# MMI.net
KiCad netlist of a schematic drawn in Altium Designer
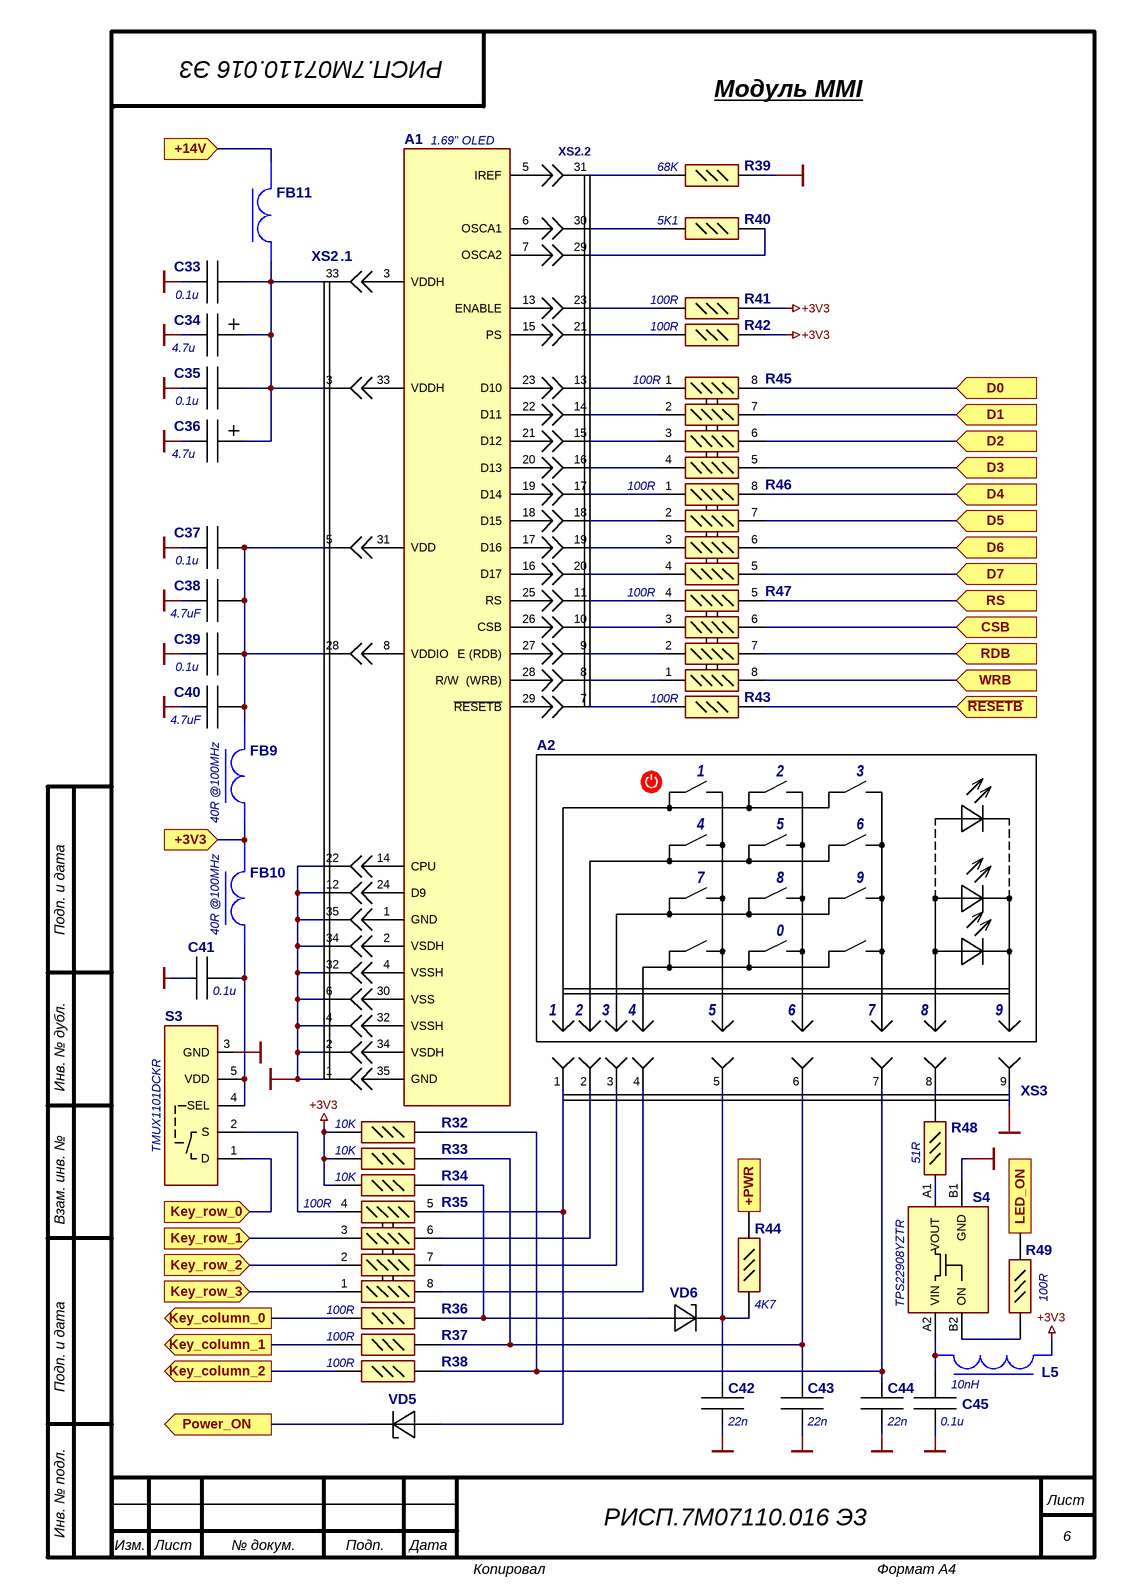
[diagram p0: Модуль MMI.SchDoc]

(export (version "E")
  (design (tool "Eeschema 10.0.6"))
  (components
    (comp (ref "A1")
      (value "1.69\" OLED")
      (fields (field (name "MANUFACTURER_PART_NUMBER") "NHD-1.69-160128G"))
      (libsource (lib "Other") (part "NHD-1.69-160128G"))
    )
    (comp (ref "A2")
      (value "~")
      (fields (field (name "MANUFACTURER_PART_NUMBER") "Клавиатура 5042 ТЕИЯ.464511.002 ТЗ"))
      (libsource (lib "Other") (part "Клавиатура 3x4 (Заказ №...)"))
    )
    (comp (ref "C33")
      (value "0.1u")
      (footprint ":CAP0402 100x50x50")
      (description "±10% 25V Ceramic Capacitor X7R 0402 (1005 Metric)")
      (fields
        (field (name "MANUFACTURER_PART_NUMBER") "GRM155R71E104KE14J")
        (field (name "MOUSER PART NUMBER") "81-GRM155R71E104KE4J")
      )
      (libsource (lib "Capacitors 0402") (part "GRM155R71E104KE14J"))
    )
    (comp (ref "C34")
      (value "4.7u")
      (footprint ":CAP1206 C3216-18")
      (description "4.7µF Molded Tantalum Capacitors 25V 1206 (3216 Metric) 50mOhm")
      (fields (field (name "MANUFACTURER_PART_NUMBER") "T491A475K025AT"))
      (libsource (lib "Capacitors 1206") (part "T491A475K025AT"))
    )
    (comp (ref "C35")
      (value "0.1u")
      (footprint ":CAP0402 100x50x50")
      (description "±10% 25V Ceramic Capacitor X7R 0402 (1005 Metric)")
      (fields
        (field (name "MANUFACTURER_PART_NUMBER") "GRM155R71E104KE14J")
        (field (name "MOUSER PART NUMBER") "81-GRM155R71E104KE4J")
      )
      (libsource (lib "Capacitors 0402") (part "GRM155R71E104KE14J"))
    )
    (comp (ref "C36")
      (value "4.7u")
      (footprint ":CAP1206 C3216-18")
      (description "4.7µF Molded Tantalum Capacitors 25V 1206 (3216 Metric) 50mOhm")
      (fields (field (name "MANUFACTURER_PART_NUMBER") "T491A475K025AT"))
      (libsource (lib "Capacitors 1206") (part "T491A475K025AT"))
    )
    (comp (ref "C37")
      (value "0.1u")
      (footprint ":CAP0402 100x50x50")
      (description "±10% 25V Ceramic Capacitor X7R 0402 (1005 Metric)")
      (fields
        (field (name "MANUFACTURER_PART_NUMBER") "GRM155R71E104KE14J")
        (field (name "MOUSER PART NUMBER") "81-GRM155R71E104KE4J")
      )
      (libsource (lib "Capacitors 0402") (part "GRM155R71E104KE14J"))
    )
    (comp (ref "C38")
      (value "4.7uF")
      (footprint ":CAP0805 C2012X125")
      (description "CAP CER 4.7uF 25V X7R 0805")
      (fields (field (name "MANUFACTURER_PART_NUMBER") "GRM21BZ71E475KE15L"))
      (libsource (lib "Capacitors 0805") (part "GRM21BZ71E475KE15L"))
    )
    (comp (ref "C39")
      (value "0.1u")
      (footprint ":CAP0402 100x50x50")
      (description "±10% 25V Ceramic Capacitor X7R 0402 (1005 Metric)")
      (fields
        (field (name "MANUFACTURER_PART_NUMBER") "GRM155R71E104KE14J")
        (field (name "MOUSER PART NUMBER") "81-GRM155R71E104KE4J")
      )
      (libsource (lib "Capacitors 0402") (part "GRM155R71E104KE14J"))
    )
    (comp (ref "C40")
      (value "4.7uF")
      (footprint ":CAP0805 C2012X125")
      (description "CAP CER 4.7uF 25V X7R 0805")
      (fields (field (name "MANUFACTURER_PART_NUMBER") "GRM21BZ71E475KE15L"))
      (libsource (lib "Capacitors 0805") (part "GRM21BZ71E475KE15L"))
    )
    (comp (ref "C41")
      (value "0.1u")
      (footprint ":CAP0402 100x50x50")
      (description "±10% 25V Ceramic Capacitor X7R 0402 (1005 Metric)")
      (fields
        (field (name "MANUFACTURER_PART_NUMBER") "GRM155R71E104KE14J")
        (field (name "MOUSER PART NUMBER") "81-GRM155R71E104KE4J")
      )
      (libsource (lib "Capacitors 0402") (part "GRM155R71E104KE14J"))
    )
    (comp (ref "C42")
      (value "22n")
      (footprint ":CAP0402 100x50x50")
      (description "CAP CER  25V X7R 0402")
      (fields (field (name "MANUFACTURER_PART_NUMBER") "GCM155R71E223KA55D"))
      (libsource (lib "Capacitors 0402") (part "GCM155R71E223KA55D"))
    )
    (comp (ref "C43")
      (value "22n")
      (footprint ":CAP0402 100x50x50")
      (description "CAP CER  25V X7R 0402")
      (fields (field (name "MANUFACTURER_PART_NUMBER") "GCM155R71E223KA55D"))
      (libsource (lib "Capacitors 0402") (part "GCM155R71E223KA55D"))
    )
    (comp (ref "C44")
      (value "22n")
      (footprint ":CAP0402 100x50x50")
      (description "CAP CER  25V X7R 0402")
      (fields (field (name "MANUFACTURER_PART_NUMBER") "GCM155R71E223KA55D"))
      (libsource (lib "Capacitors 0402") (part "GCM155R71E223KA55D"))
    )
    (comp (ref "C45")
      (value "0.1u")
      (footprint ":CAP0402 100x50x50")
      (description "±10% 25V Ceramic Capacitor X7R 0402 (1005 Metric)")
      (fields
        (field (name "MANUFACTURER_PART_NUMBER") "GRM155R71E104KE14J")
        (field (name "MOUSER PART NUMBER") "81-GRM155R71E104KE4J")
      )
      (libsource (lib "Capacitors 0402") (part "GRM155R71E104KE14J"))
    )
    (comp (ref "FB9")
      (value "40R @100MHz")
      (footprint ":FER MMZ1005Y400CTD25")
      (description "40 Ohms @ 100MHz 1 Signal Line Ferrite Bead 0402 (1005 Metric) 550mA 100mOhm")
      (fields
        (field (name "MANUFACTURER_PART_NUMBER") "MMZ1005Y400CTD25")
        (field (name "MOUSER PART NUMBER") "810-MMZ1005Y400CTD25")
      )
      (libsource (lib "Ferrite Bead") (part "MMZ1005Y400CTD25"))
    )
    (comp (ref "FB10")
      (value "40R @100MHz")
      (footprint ":FER MMZ1005Y400CTD25")
      (description "40 Ohms @ 100MHz 1 Signal Line Ferrite Bead 0402 (1005 Metric) 550mA 100mOhm")
      (fields
        (field (name "MANUFACTURER_PART_NUMBER") "MMZ1005Y400CTD25")
        (field (name "MOUSER PART NUMBER") "810-MMZ1005Y400CTD25")
      )
      (libsource (lib "Ferrite Bead") (part "MMZ1005Y400CTD25"))
    )
    (comp (ref "FB11")
      (value "40R @100MHz")
      (footprint ":FER MMZ1005Y400CTD25")
      (description "40 Ohms @ 100MHz 1 Signal Line Ferrite Bead 0402 (1005 Metric) 550mA 100mOhm")
      (fields
        (field (name "MANUFACTURER_PART_NUMBER") "MMZ1005Y400CTD25")
        (field (name "MOUSER PART NUMBER") "810-MMZ1005Y400CTD25")
      )
      (libsource (lib "Ferrite Bead") (part "MMZ1005Y400CTD25"))
    )
    (comp (ref "L5")
      (value "10nH")
      (footprint ":IND 0402")
      (description "Unshielded Multilayer Inductor 0402 5%")
      (fields (field (name "MANUFACTURER_PART_NUMBER") "LQG15HN10NJ02D"))
      (libsource (lib "Inductance 0402") (part "LQG15HN10NJ02D"))
    )
    (comp (ref "R32")
      (value "RC0402FR-07")
      (footprint ":RES0402")
      (fields (field (name "MANUFACTURER_PART_NUMBER (PART 2: VALUE)") "10K"))
      (libsource (lib "") (part "RC0402FR-07_1"))
    )
    (comp (ref "R33")
      (value "RC0402FR-07")
      (footprint ":RES0402")
      (fields (field (name "MANUFACTURER_PART_NUMBER (PART 2: VALUE)") "10K"))
      (libsource (lib "") (part "RC0402FR-07_1"))
    )
    (comp (ref "R34")
      (value "RC0402FR-07")
      (footprint ":RES0402")
      (fields (field (name "MANUFACTURER_PART_NUMBER (PART 2: VALUE)") "10K"))
      (libsource (lib "") (part "RC0402FR-07_1"))
    )
    (comp (ref "R35")
      (value "100R")
      (footprint ":RES0402x4")
      (fields
        (field (name "MANUFACTURER_PART_NUMBER") "EXB-N8V101JX")
        (field (name "MOUSER PART NUMBER") "667-EXB-N8V101JX")
      )
      (libsource (lib "Resistors Arrays") (part "EXB-N8V101JX"))
    )
    (comp (ref "R36")
      (value "RC0402FR-07")
      (footprint ":RES0402")
      (fields (field (name "MANUFACTURER_PART_NUMBER (PART 2: VALUE)") "100R"))
      (libsource (lib "") (part "RC0402FR-07_2"))
    )
    (comp (ref "R37")
      (value "RC0402FR-07")
      (footprint ":RES0402")
      (fields (field (name "MANUFACTURER_PART_NUMBER (PART 2: VALUE)") "100R"))
      (libsource (lib "") (part "RC0402FR-07_2"))
    )
    (comp (ref "R38")
      (value "RC0402FR-07")
      (footprint ":RES0402")
      (fields (field (name "MANUFACTURER_PART_NUMBER (PART 2: VALUE)") "100R"))
      (libsource (lib "") (part "RC0402FR-07_2"))
    )
    (comp (ref "R39")
      (value "RC0402FR-07")
      (footprint ":RES0402")
      (fields (field (name "MANUFACTURER_PART_NUMBER (PART 2: VALUE)") "68K"))
      (libsource (lib "") (part "RC0402FR-07_2"))
    )
    (comp (ref "R40")
      (value "RC0402FR-07")
      (footprint ":RES0402")
      (fields (field (name "MANUFACTURER_PART_NUMBER (PART 2: VALUE)") "5K1"))
      (libsource (lib "") (part "RC0402FR-07_2"))
    )
    (comp (ref "R41")
      (value "RC0402FR-07")
      (footprint ":RES0402")
      (fields (field (name "MANUFACTURER_PART_NUMBER (PART 2: VALUE)") "100R"))
      (libsource (lib "") (part "RC0402FR-07_2"))
    )
    (comp (ref "R42")
      (value "RC0402FR-07")
      (footprint ":RES0402")
      (fields (field (name "MANUFACTURER_PART_NUMBER (PART 2: VALUE)") "100R"))
      (libsource (lib "") (part "RC0402FR-07_2"))
    )
    (comp (ref "R43")
      (value "RC0402FR-07")
      (footprint ":RES0402")
      (fields (field (name "MANUFACTURER_PART_NUMBER (PART 2: VALUE)") "100R"))
      (libsource (lib "") (part "RC0402FR-07_2"))
    )
    (comp (ref "R44")
      (value "RC0402FR-07")
      (footprint ":RES0402")
      (fields (field (name "MANUFACTURER_PART_NUMBER (PART 2: VALUE)") "4K7"))
      (libsource (lib "Resistors 0402") (part "RC0402FR-07"))
    )
    (comp (ref "R45")
      (value "100R")
      (footprint ":RES0402x4")
      (fields
        (field (name "MANUFACTURER_PART_NUMBER") "EXB-N8V101JX")
        (field (name "MOUSER PART NUMBER") "667-EXB-N8V101JX")
      )
      (libsource (lib "") (part "EXB-N8V101JX_1"))
    )
    (comp (ref "R46")
      (value "100R")
      (footprint ":RES0402x4")
      (fields
        (field (name "MANUFACTURER_PART_NUMBER") "EXB-N8V101JX")
        (field (name "MOUSER PART NUMBER") "667-EXB-N8V101JX")
      )
      (libsource (lib "") (part "EXB-N8V101JX_1"))
    )
    (comp (ref "R47")
      (value "100R")
      (footprint ":RES0402x4")
      (fields
        (field (name "MANUFACTURER_PART_NUMBER") "EXB-N8V101JX")
        (field (name "MOUSER PART NUMBER") "667-EXB-N8V101JX")
      )
      (libsource (lib "Resistors Arrays") (part "EXB-N8V101JX"))
    )
    (comp (ref "R48")
      (value "RC0402FR-07")
      (footprint ":RES0402")
      (fields (field (name "MANUFACTURER_PART_NUMBER (PART 2: VALUE)") "51R"))
      (libsource (lib "Resistors 0402") (part "RC0402FR-07"))
    )
    (comp (ref "R49")
      (value "RC0402FR-07")
      (footprint ":RES0402")
      (fields (field (name "MANUFACTURER_PART_NUMBER (PART 2: VALUE)") "100R"))
      (libsource (lib "Resistors 0402") (part "RC0402FR-07"))
    )
    (comp (ref "S3")
      (value "TMUX1101DCKR")
      (footprint ":SC70 (5) P200X125X10")
      (description "SPST Switch Bidir. 1.8 Ω 30mA 300MHz")
      (fields (field (name "MOUSER PART NUMBER") "595-TMUX1101DCKR"))
      (libsource (lib "Switching and Relays") (part "TMUX1101DCKR"))
    )
    (comp (ref "S4")
      (value "TPS22908YZTR")
      (footprint ":BGA4 P90X90X50")
      (description "SPST Switch 3.6-V, 1-A, 28-mΩ")
      (fields (field (name "MOUSER PART NUMBER") "595-TPS22908YZTR"))
      (libsource (lib "Switching and Relays") (part "TPS22908YZTR"))
    )
    (comp (ref "VD5")
      (value "30V 0.1A")
      (footprint ":DIODE SOD-923F")
      (description "Diodes Schottky 0402 30V 0.1A")
      (fields
        (field (name "MANUFACTURER_PART_NUMBER") "CDBQR0130R")
        (field (name "MOUSER PART NUMBER") "750-CDBQR0130R")
      )
      (libsource (lib "Diodes 0402") (part "CDBQR0130R"))
    )
    (comp (ref "VD6")
      (value "30V 0.1A")
      (footprint ":DIODE SOD-923F")
      (description "Diodes Schottky 0402 30V 0.1A")
      (fields
        (field (name "MANUFACTURER_PART_NUMBER") "CDBQR0130R")
        (field (name "MOUSER PART NUMBER") "750-CDBQR0130R")
      )
      (libsource (lib "Diodes 0402") (part "CDBQR0130R"))
    )
    (comp (ref "XS2")
      (value "0541043531")
      (footprint "ZIK lib:541043531")
      (description "Rotary Backlock Connector 35-pin 0.5mm Pitch, Top side Contact")
      (fields (field (name "MOUSER2 PART NUMBER") "538-54104-3531"))
      (libsource (lib "Connectors") (part "0541043531"))
    )
    (comp (ref "XS3")
      (value "XF3M-0915-1B")
      (footprint ":CON XF3M-0915-1B")
      (description "Rotary Backlock Connector 35-pin 0.5mm Pitch, Dual sided Contact")
      (libsource (lib "Connectors") (part "XF3M-0915-1B"))
    )
  )
  (nets
    (net (code "1") (name "+3V3") (class "Default")
      (node (ref "FB10") (pin "2") (pinfunction "2_2") (pintype "passive"))
      (node (ref "FB9") (pin "1") (pinfunction "1_1") (pintype "passive"))
      (node (ref "L5") (pin "2") (pinfunction "2_2") (pintype "passive"))
      (node (ref "R32") (pin "2") (pinfunction "2_2") (pintype "passive"))
      (node (ref "R33") (pin "2") (pinfunction "2_2") (pintype "passive"))
      (node (ref "R34") (pin "2") (pinfunction "2_2") (pintype "passive"))
      (node (ref "R41") (pin "2") (pinfunction "2_2") (pintype "passive"))
      (node (ref "R42") (pin "2") (pinfunction "2_2") (pintype "passive"))
    )
    (net (code "2") (name "/+14V") (class "Default")
      (node (ref "FB11") (pin "2") (pinfunction "2_2") (pintype "passive"))
    )
    (net (code "3") (name "/+PWR") (class "Default")
      (node (ref "R44") (pin "1") (pinfunction "1_1") (pintype "passive"))
    )
    (net (code "4") (name "/CSB") (class "Default")
      (node (ref "R47") (pin "6") (pinfunction "6_6") (pintype "passive"))
    )
    (net (code "5") (name "/D0") (class "Default")
      (node (ref "R45") (pin "8") (pinfunction "8_8") (pintype "passive"))
    )
    (net (code "6") (name "/D1") (class "Default")
      (node (ref "R45") (pin "7") (pinfunction "7_7") (pintype "passive"))
    )
    (net (code "7") (name "/D2") (class "Default")
      (node (ref "R45") (pin "6") (pinfunction "6_6") (pintype "passive"))
    )
    (net (code "8") (name "/D3") (class "Default")
      (node (ref "R45") (pin "5") (pinfunction "5_5") (pintype "passive"))
    )
    (net (code "9") (name "/D4") (class "Default")
      (node (ref "R46") (pin "8") (pinfunction "8_8") (pintype "passive"))
    )
    (net (code "10") (name "/D5") (class "Default")
      (node (ref "R46") (pin "7") (pinfunction "7_7") (pintype "passive"))
    )
    (net (code "11") (name "/D6") (class "Default")
      (node (ref "R46") (pin "6") (pinfunction "6_6") (pintype "passive"))
    )
    (net (code "12") (name "/D7") (class "Default")
      (node (ref "R46") (pin "5") (pinfunction "5_5") (pintype "passive"))
    )
    (net (code "13") (name "/Key_column_0") (class "Default")
      (node (ref "R36") (pin "1") (pinfunction "1_1") (pintype "passive"))
    )
    (net (code "14") (name "/Key_column_1") (class "Default")
      (node (ref "R37") (pin "1") (pinfunction "1_1") (pintype "passive"))
    )
    (net (code "15") (name "/Key_column_2") (class "Default")
      (node (ref "R38") (pin "1") (pinfunction "1_1") (pintype "passive"))
    )
    (net (code "16") (name "/Key_row_0") (class "Default")
      (node (ref "S3") (pin "1") (pinfunction "D_1") (pintype "passive"))
    )
    (net (code "17") (name "/Key_row_1") (class "Default")
      (node (ref "R35") (pin "3") (pinfunction "3_3") (pintype "passive"))
    )
    (net (code "18") (name "/Key_row_2") (class "Default")
      (node (ref "R35") (pin "2") (pinfunction "2_2") (pintype "passive"))
    )
    (net (code "19") (name "/Key_row_3") (class "Default")
      (node (ref "R35") (pin "1") (pinfunction "1_1") (pintype "passive"))
    )
    (net (code "20") (name "/LED_ON") (class "Default")
      (node (ref "R49") (pin "1") (pinfunction "1_1") (pintype "passive"))
    )
    (net (code "21") (name "/Power_ON") (class "Default")
      (node (ref "VD5") (pin "1") (pinfunction "K_1") (pintype "passive"))
    )
    (net (code "22") (name "/RDB") (class "Default")
      (node (ref "R47") (pin "7") (pinfunction "7_7") (pintype "passive"))
    )
    (net (code "23") (name "/RS") (class "Default")
      (node (ref "R47") (pin "5") (pinfunction "5_5") (pintype "passive"))
    )
    (net (code "24") (name "/WRB") (class "Default")
      (node (ref "R47") (pin "8") (pinfunction "8_8") (pintype "passive"))
    )
    (net (code "25") (name "/~{RESETB}") (class "Default")
      (node (ref "R43") (pin "2") (pinfunction "2_2") (pintype "passive"))
    )
    (net (code "26") (name "GND") (class "Default")
      (node (ref "C33") (pin "1") (pinfunction "1_1") (pintype "passive"))
      (node (ref "C34") (pin "2") (pinfunction "2_2") (pintype "passive"))
      (node (ref "C35") (pin "1") (pinfunction "1_1") (pintype "passive"))
      (node (ref "C36") (pin "2") (pinfunction "2_2") (pintype "passive"))
      (node (ref "C37") (pin "1") (pinfunction "1_1") (pintype "passive"))
      (node (ref "C38") (pin "2") (pinfunction "2_2") (pintype "passive"))
      (node (ref "C39") (pin "1") (pinfunction "1_1") (pintype "passive"))
      (node (ref "C40") (pin "2") (pinfunction "2_2") (pintype "passive"))
      (node (ref "C41") (pin "1") (pinfunction "1_1") (pintype "passive"))
      (node (ref "C42") (pin "1") (pinfunction "1_1") (pintype "passive"))
      (node (ref "C43") (pin "1") (pinfunction "1_1") (pintype "passive"))
      (node (ref "C44") (pin "1") (pinfunction "1_1") (pintype "passive"))
      (node (ref "C45") (pin "2") (pinfunction "2_2") (pintype "passive"))
      (node (ref "R39") (pin "2") (pinfunction "2_2") (pintype "passive"))
      (node (ref "S3") (pin "3") (pinfunction "GND_3") (pintype "passive"))
      (node (ref "S4") (pin "B1") (pinfunction "GND_B1") (pintype "passive"))
      (node (ref "XS2") (pin "1") (pintype "passive"))
      (node (ref "XS2") (pin "12") (pintype "passive"))
      (node (ref "XS2") (pin "2") (pintype "passive"))
      (node (ref "XS2") (pin "22") (pintype "passive"))
      (node (ref "XS2") (pin "32") (pintype "passive"))
      (node (ref "XS2") (pin "34") (pintype "passive"))
      (node (ref "XS2") (pin "35") (pintype "passive"))
      (node (ref "XS2") (pin "4") (pintype "passive"))
      (node (ref "XS2") (pin "6") (pintype "passive"))
      (node (ref "XS3") (pin "9") (pinfunction "9_9") (pintype "passive"))
    )
    (net (code "27") (name "Net-(C34-+)") (class "Default")
      (node (ref "C33") (pin "2") (pinfunction "2_2") (pintype "passive"))
      (node (ref "C34") (pin "1") (pinfunction "+_1") (pintype "passive"))
      (node (ref "C35") (pin "2") (pinfunction "2_2") (pintype "passive"))
      (node (ref "C36") (pin "1") (pinfunction "+_1") (pintype "passive"))
      (node (ref "FB11") (pin "1") (pinfunction "1_1") (pintype "passive"))
      (node (ref "XS2") (pin "3") (pintype "passive"))
      (node (ref "XS2") (pin "33") (pintype "passive"))
    )
    (net (code "28") (name "Net-(C37-Pad2)") (class "Default")
      (node (ref "C37") (pin "2") (pinfunction "2_2") (pintype "passive"))
      (node (ref "C38") (pin "1") (pinfunction "1_1") (pintype "passive"))
      (node (ref "C39") (pin "2") (pinfunction "2_2") (pintype "passive"))
      (node (ref "C40") (pin "1") (pinfunction "1_1") (pintype "passive"))
      (node (ref "FB9") (pin "2") (pinfunction "2_2") (pintype "passive"))
      (node (ref "XS2") (pin "28") (pintype "passive"))
      (node (ref "XS2") (pin "5") (pintype "passive"))
    )
    (net (code "29") (name "Net-(C43-Pad2)") (class "Default")
      (node (ref "C43") (pin "2") (pinfunction "2_2") (pintype "passive"))
      (node (ref "R33") (pin "1") (pinfunction "1_1") (pintype "passive"))
      (node (ref "R37") (pin "2") (pinfunction "2_2") (pintype "passive"))
      (node (ref "XS3") (pin "6") (pinfunction "6_6") (pintype "passive"))
    )
    (net (code "30") (name "Net-(C44-Pad2)") (class "Default")
      (node (ref "C44") (pin "2") (pinfunction "2_2") (pintype "passive"))
      (node (ref "R32") (pin "1") (pinfunction "1_1") (pintype "passive"))
      (node (ref "R38") (pin "2") (pinfunction "2_2") (pintype "passive"))
      (node (ref "XS3") (pin "7") (pinfunction "7_7") (pintype "passive"))
    )
    (net (code "31") (name "Net-(R35-Pad7)") (class "Default")
      (node (ref "R35") (pin "7") (pinfunction "7_7") (pintype "passive"))
      (node (ref "XS3") (pin "3") (pinfunction "3_3") (pintype "passive"))
    )
    (net (code "32") (name "Net-(R35-Pad8)") (class "Default")
      (node (ref "R35") (pin "8") (pinfunction "8_8") (pintype "passive"))
      (node (ref "XS3") (pin "4") (pinfunction "4_4") (pintype "passive"))
    )
    (net (code "33") (name "Net-(R39-Pad1)") (class "Default")
      (node (ref "R39") (pin "1") (pinfunction "1_1") (pintype "passive"))
      (node (ref "XS2") (pin "31") (pintype "passive"))
    )
    (net (code "34") (name "Net-(R40-Pad1)") (class "Default")
      (node (ref "R40") (pin "1") (pinfunction "1_1") (pintype "passive"))
      (node (ref "XS2") (pin "30") (pintype "passive"))
    )
    (net (code "35") (name "Net-(R40-Pad2)") (class "Default")
      (node (ref "R40") (pin "2") (pinfunction "2_2") (pintype "passive"))
      (node (ref "XS2") (pin "29") (pintype "passive"))
    )
    (net (code "36") (name "Net-(R41-Pad1)") (class "Default")
      (node (ref "R41") (pin "1") (pinfunction "1_1") (pintype "passive"))
      (node (ref "XS2") (pin "23") (pintype "passive"))
    )
    (net (code "37") (name "Net-(R42-Pad1)") (class "Default")
      (node (ref "R42") (pin "1") (pinfunction "1_1") (pintype "passive"))
      (node (ref "XS2") (pin "21") (pintype "passive"))
    )
    (net (code "38") (name "Net-(R43-Pad1)") (class "Default")
      (node (ref "R43") (pin "1") (pinfunction "1_1") (pintype "passive"))
      (node (ref "XS2") (pin "7") (pintype "passive"))
    )
    (net (code "39") (name "Net-(R45-Pad1)") (class "Default")
      (node (ref "R45") (pin "1") (pinfunction "1_1") (pintype "passive"))
      (node (ref "XS2") (pin "13") (pintype "passive"))
    )
    (net (code "40") (name "Net-(R45-Pad2)") (class "Default")
      (node (ref "R45") (pin "2") (pinfunction "2_2") (pintype "passive"))
      (node (ref "XS2") (pin "14") (pintype "passive"))
    )
    (net (code "41") (name "Net-(R45-Pad3)") (class "Default")
      (node (ref "R45") (pin "3") (pinfunction "3_3") (pintype "passive"))
      (node (ref "XS2") (pin "15") (pintype "passive"))
    )
    (net (code "42") (name "Net-(R45-Pad4)") (class "Default")
      (node (ref "R45") (pin "4") (pinfunction "4_4") (pintype "passive"))
      (node (ref "XS2") (pin "16") (pintype "passive"))
    )
    (net (code "43") (name "Net-(R46-Pad1)") (class "Default")
      (node (ref "R46") (pin "1") (pinfunction "1_1") (pintype "passive"))
      (node (ref "XS2") (pin "17") (pintype "passive"))
    )
    (net (code "44") (name "Net-(R46-Pad2)") (class "Default")
      (node (ref "R46") (pin "2") (pinfunction "2_2") (pintype "passive"))
      (node (ref "XS2") (pin "18") (pintype "passive"))
    )
    (net (code "45") (name "Net-(R46-Pad3)") (class "Default")
      (node (ref "R46") (pin "3") (pinfunction "3_3") (pintype "passive"))
      (node (ref "XS2") (pin "19") (pintype "passive"))
    )
    (net (code "46") (name "Net-(R46-Pad4)") (class "Default")
      (node (ref "R46") (pin "4") (pinfunction "4_4") (pintype "passive"))
      (node (ref "XS2") (pin "20") (pintype "passive"))
    )
    (net (code "47") (name "Net-(R47-Pad1)") (class "Default")
      (node (ref "R47") (pin "1") (pinfunction "1_1") (pintype "passive"))
      (node (ref "XS2") (pin "8") (pintype "passive"))
    )
    (net (code "48") (name "Net-(R47-Pad2)") (class "Default")
      (node (ref "R47") (pin "2") (pinfunction "2_2") (pintype "passive"))
      (node (ref "XS2") (pin "9") (pintype "passive"))
    )
    (net (code "49") (name "Net-(R47-Pad3)") (class "Default")
      (node (ref "R47") (pin "3") (pinfunction "3_3") (pintype "passive"))
      (node (ref "XS2") (pin "10") (pintype "passive"))
    )
    (net (code "50") (name "Net-(R47-Pad4)") (class "Default")
      (node (ref "R47") (pin "4") (pinfunction "4_4") (pintype "passive"))
      (node (ref "XS2") (pin "11") (pintype "passive"))
    )
    (net (code "51") (name "Net-(R48-Pad1)") (class "Default")
      (node (ref "R48") (pin "1") (pinfunction "1_1") (pintype "passive"))
      (node (ref "XS3") (pin "8") (pinfunction "8_8") (pintype "passive"))
    )
    (net (code "52") (name "Net-(S3-S)") (class "Default")
      (node (ref "R35") (pin "4") (pinfunction "4_4") (pintype "passive"))
      (node (ref "S3") (pin "2") (pinfunction "S_2") (pintype "passive"))
    )
    (net (code "53") (name "Net-(S3-SEL)") (class "Default")
      (node (ref "C41") (pin "2") (pinfunction "2_2") (pintype "passive"))
      (node (ref "FB10") (pin "1") (pinfunction "1_1") (pintype "passive"))
      (node (ref "S3") (pin "4") (pinfunction "SEL_4") (pintype "passive"))
      (node (ref "S3") (pin "5") (pinfunction "VDD_5") (pintype "passive"))
    )
    (net (code "54") (name "Net-(S4-ON)") (class "Default")
      (node (ref "R49") (pin "2") (pinfunction "2_2") (pintype "passive"))
      (node (ref "S4") (pin "B2") (pinfunction "ON_B2") (pintype "passive"))
    )
    (net (code "55") (name "Net-(S4-VIN)") (class "Default")
      (node (ref "C45") (pin "1") (pinfunction "1_1") (pintype "passive"))
      (node (ref "L5") (pin "1") (pinfunction "1_1") (pintype "passive"))
      (node (ref "S4") (pin "A2") (pinfunction "VIN_A2") (pintype "passive"))
    )
    (net (code "56") (name "Net-(S4-VOUT)") (class "Default")
      (node (ref "R48") (pin "2") (pinfunction "2_2") (pintype "passive"))
      (node (ref "S4") (pin "A1") (pinfunction "VOUT_A1") (pintype "passive"))
    )
    (net (code "57") (name "Net-(VD5-A)") (class "Default")
      (node (ref "R35") (pin "5") (pinfunction "5_5") (pintype "passive"))
      (node (ref "VD5") (pin "2") (pinfunction "A_2") (pintype "passive"))
      (node (ref "XS3") (pin "1") (pinfunction "1_1") (pintype "passive"))
    )
    (net (code "58") (name "Net-(VD6-A)") (class "Default")
      (node (ref "R34") (pin "1") (pinfunction "1_1") (pintype "passive"))
      (node (ref "R36") (pin "2") (pinfunction "2_2") (pintype "passive"))
      (node (ref "VD6") (pin "2") (pinfunction "A_2") (pintype "passive"))
    )
    (net (code "59") (name "Net-(VD6-K)") (class "Default")
      (node (ref "C42") (pin "2") (pinfunction "2_2") (pintype "passive"))
      (node (ref "R44") (pin "2") (pinfunction "2_2") (pintype "passive"))
      (node (ref "VD6") (pin "1") (pinfunction "K_1") (pintype "passive"))
      (node (ref "XS3") (pin "5") (pinfunction "5_5") (pintype "passive"))
    )
    (net (code "60") (name "Net-(XS3-ч)") (class "Default")
      (node (ref "R35") (pin "6") (pinfunction "6_6") (pintype "passive"))
      (node (ref "XS3") (pin "2") (pinfunction "ч_2") (pintype "passive"))
    )
    (net (code "61") (name "unconnected-(A1-CPU-Pad14)") (class "Default")
      (node (ref "A1") (pin "14") (pinfunction "CPU_14") (pintype "passive"))
    )
    (net (code "62") (name "unconnected-(A1-CSB-Pad26)") (class "Default")
      (node (ref "A1") (pin "26") (pinfunction "CSB_26") (pintype "passive"))
    )
    (net (code "63") (name "unconnected-(A1-D9-Pad24)") (class "Default")
      (node (ref "A1") (pin "24") (pinfunction "D9_24") (pintype "passive"))
    )
    (net (code "64") (name "unconnected-(A1-D10-Pad23)") (class "Default")
      (node (ref "A1") (pin "23") (pinfunction "D10_23") (pintype "passive"))
    )
    (net (code "65") (name "unconnected-(A1-D11-Pad22)") (class "Default")
      (node (ref "A1") (pin "22") (pinfunction "D11_22") (pintype "passive"))
    )
    (net (code "66") (name "unconnected-(A1-D12-Pad21)") (class "Default")
      (node (ref "A1") (pin "21") (pinfunction "D12_21") (pintype "passive"))
    )
    (net (code "67") (name "unconnected-(A1-D13-Pad20)") (class "Default")
      (node (ref "A1") (pin "20") (pinfunction "D13_20") (pintype "passive"))
    )
    (net (code "68") (name "unconnected-(A1-D14-Pad19)") (class "Default")
      (node (ref "A1") (pin "19") (pinfunction "D14_19") (pintype "passive"))
    )
    (net (code "69") (name "unconnected-(A1-D15-Pad18)") (class "Default")
      (node (ref "A1") (pin "18") (pinfunction "D15_18") (pintype "passive"))
    )
    (net (code "70") (name "unconnected-(A1-D16-Pad17)") (class "Default")
      (node (ref "A1") (pin "17") (pinfunction "D16_17") (pintype "passive"))
    )
    (net (code "71") (name "unconnected-(A1-D17-Pad16)") (class "Default")
      (node (ref "A1") (pin "16") (pinfunction "D17_16") (pintype "passive"))
    )
    (net (code "72") (name "unconnected-(A1-ENABLE-Pad13)") (class "Default")
      (node (ref "A1") (pin "13") (pinfunction "ENABLE_13") (pintype "passive"))
    )
    (net (code "73") (name "unconnected-(A1-E_(RDB)-Pad27)") (class "Default")
      (node (ref "A1") (pin "27") (pinfunction "E_(RDB)_27") (pintype "passive"))
    )
    (net (code "74") (name "unconnected-(A1-GND-Pad1)") (class "Default")
      (node (ref "A1") (pin "1") (pinfunction "GND_1") (pintype "passive"))
    )
    (net (code "75") (name "unconnected-(A1-GND-Pad35)") (class "Default")
      (node (ref "A1") (pin "35") (pinfunction "GND_35") (pintype "passive"))
    )
    (net (code "76") (name "unconnected-(A1-IREF-Pad5)") (class "Default")
      (node (ref "A1") (pin "5") (pinfunction "IREF_5") (pintype "passive"))
    )
    (net (code "77") (name "unconnected-(A1-OSCA1-Pad6)") (class "Default")
      (node (ref "A1") (pin "6") (pinfunction "OSCA1_6") (pintype "passive"))
    )
    (net (code "78") (name "unconnected-(A1-OSCA2-Pad7)") (class "Default")
      (node (ref "A1") (pin "7") (pinfunction "OSCA2_7") (pintype "passive"))
    )
    (net (code "79") (name "unconnected-(A1-PS-Pad15)") (class "Default")
      (node (ref "A1") (pin "15") (pinfunction "PS_15") (pintype "passive"))
    )
    (net (code "80") (name "unconnected-(A1-RS-Pad25)") (class "Default")
      (node (ref "A1") (pin "25") (pinfunction "RS_25") (pintype "passive"))
    )
    (net (code "81") (name "unconnected-(A1-R{slash}W__(WRB)-Pad28)") (class "Default")
      (node (ref "A1") (pin "28") (pinfunction "R/W__(WRB)_28") (pintype "passive"))
    )
    (net (code "82") (name "unconnected-(A1-VDD-Pad31)") (class "Default")
      (node (ref "A1") (pin "31") (pinfunction "VDD_31") (pintype "passive"))
    )
    (net (code "83") (name "unconnected-(A1-VDDH-Pad3)") (class "Default")
      (node (ref "A1") (pin "3") (pinfunction "VDDH_3") (pintype "passive"))
    )
    (net (code "84") (name "unconnected-(A1-VDDH-Pad33)") (class "Default")
      (node (ref "A1") (pin "33") (pinfunction "VDDH_33") (pintype "passive"))
    )
    (net (code "85") (name "unconnected-(A1-VDDIO-Pad8)") (class "Default")
      (node (ref "A1") (pin "8") (pinfunction "VDDIO_8") (pintype "passive"))
    )
    (net (code "86") (name "unconnected-(A1-VSDH-Pad2)") (class "Default")
      (node (ref "A1") (pin "2") (pinfunction "VSDH_2") (pintype "passive"))
    )
    (net (code "87") (name "unconnected-(A1-VSDH-Pad34)") (class "Default")
      (node (ref "A1") (pin "34") (pinfunction "VSDH_34") (pintype "passive"))
    )
    (net (code "88") (name "unconnected-(A1-VSS-Pad30)") (class "Default")
      (node (ref "A1") (pin "30") (pinfunction "VSS_30") (pintype "passive"))
    )
    (net (code "89") (name "unconnected-(A1-VSSH-Pad4)") (class "Default")
      (node (ref "A1") (pin "4") (pinfunction "VSSH_4") (pintype "passive"))
    )
    (net (code "90") (name "unconnected-(A1-VSSH-Pad32)") (class "Default")
      (node (ref "A1") (pin "32") (pinfunction "VSSH_32") (pintype "passive"))
    )
    (net (code "91") (name "unconnected-(A1-~{RESETB}-Pad29)") (class "Default")
      (node (ref "A1") (pin "29") (pinfunction "~{RESETB}_29") (pintype "passive"))
    )
  )
)
